# vfd_controller_com.net
KiCad netlist of a schematic drawn in EAGLE
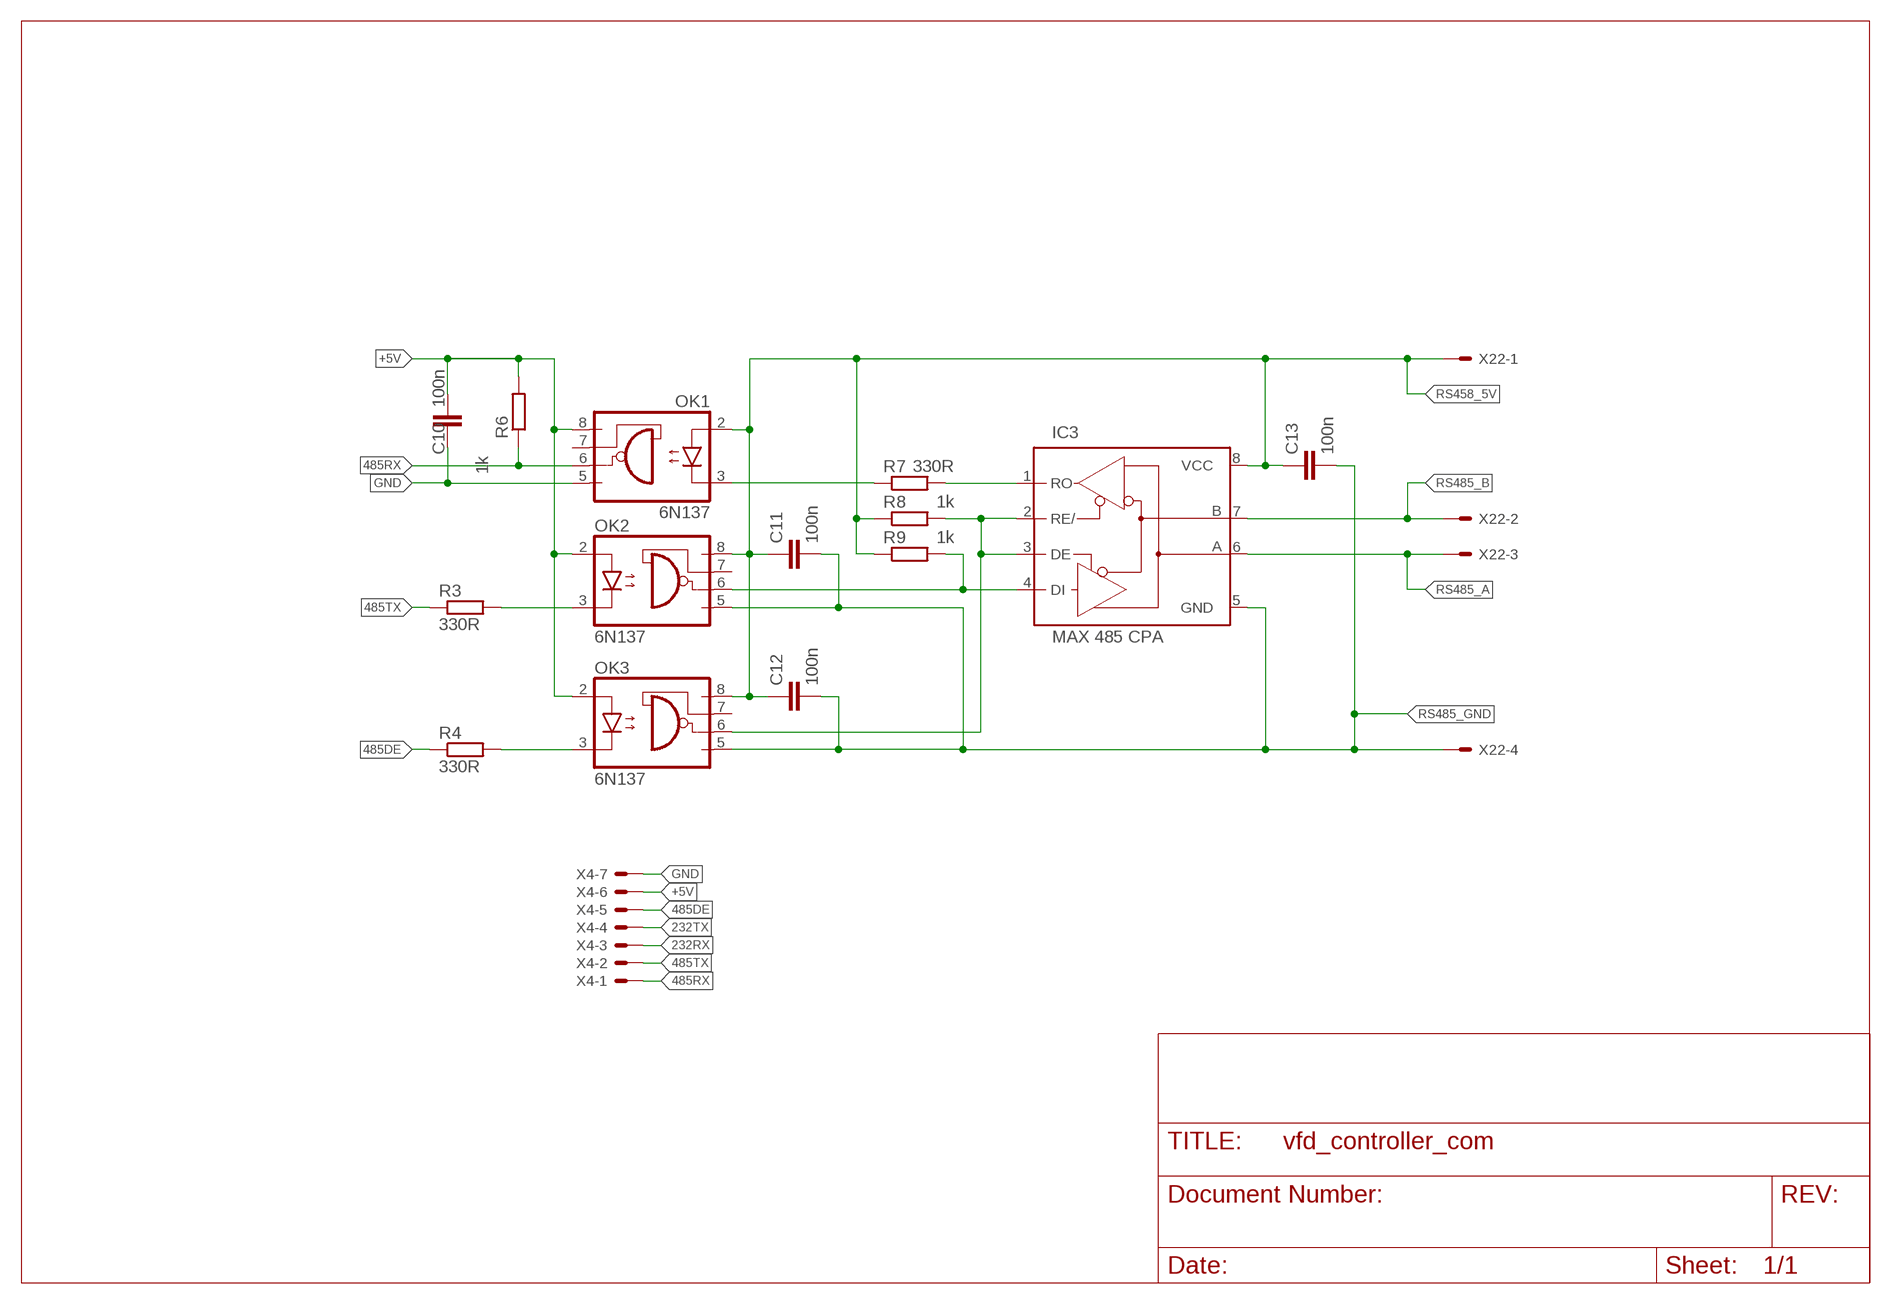
[diagram p0: schematic, sheet 1]

(export (version "E")
  (design (tool "Eeschema 10.0.6"))
  (components
    (comp (ref "C10")
      (value "100n")
      (footprint "eagle-import:C025-024X044")
      (libsource (lib "eagle-import") (part "C-EU025-024X044"))
    )
    (comp (ref "C11")
      (value "100n")
      (footprint "eagle-import:C025-024X044")
      (libsource (lib "eagle-import") (part "C-EU025-024X044"))
    )
    (comp (ref "C12")
      (value "100n")
      (footprint "eagle-import:C025-024X044")
      (libsource (lib "eagle-import") (part "C-EU025-024X044"))
    )
    (comp (ref "C13")
      (value "100n")
      (footprint "eagle-import:C025-024X044")
      (libsource (lib "eagle-import") (part "C-EU025-024X044"))
    )
    (comp (ref "IC3")
      (value "MAX 485 CPA")
      (footprint "eagle-import:DIL08")
      (libsource (lib "eagle-import") (part "MAX34PA68C"))
    )
    (comp (ref "OK1")
      (value "6N137")
      (footprint "eagle-import:DIL08")
      (libsource (lib "eagle-import") (part "6N137"))
    )
    (comp (ref "OK2")
      (value "6N137")
      (footprint "eagle-import:DIL08")
      (libsource (lib "eagle-import") (part "6N137"))
    )
    (comp (ref "OK3")
      (value "6N137")
      (footprint "eagle-import:DIL08")
      (libsource (lib "eagle-import") (part "6N137"))
    )
    (comp (ref "R3")
      (value "330R")
      (footprint "eagle-import:0204_7")
      (libsource (lib "eagle-import") (part "R-EU_0204/7"))
    )
    (comp (ref "R4")
      (value "330R")
      (footprint "eagle-import:0204_7")
      (libsource (lib "eagle-import") (part "R-EU_0204/7"))
    )
    (comp (ref "R6")
      (value "1k")
      (footprint "eagle-import:0204_7")
      (libsource (lib "eagle-import") (part "R-EU_0204/7"))
    )
    (comp (ref "R7")
      (value "330R")
      (footprint "eagle-import:0204_7")
      (libsource (lib "eagle-import") (part "R-EU_0204/7"))
    )
    (comp (ref "R8")
      (value "1k")
      (footprint "eagle-import:0204_7")
      (libsource (lib "eagle-import") (part "R-EU_0204/7"))
    )
    (comp (ref "R9")
      (value "1k")
      (footprint "eagle-import:0204_7")
      (libsource (lib "eagle-import") (part "R-EU_0204/7"))
    )
    (comp (ref "X4")
      (value "JST-XH-07-PIN-LONG-PAD")
      (footprint "eagle-import:JST-XH-07-PACKAGE-LONG-PAD")
      (libsource (lib "eagle-import") (part "JST-XH-07-PIN-LONG-PAD"))
    )
    (comp (ref "X22")
      (value "JST-XH-04-PIN-LONG-PAD")
      (footprint "eagle-import:JST-XH-04-PACKAGE-LONG-PAD")
      (libsource (lib "eagle-import") (part "JST-XH-04-PIN-LONG-PAD"))
    )
  )
  (nets
    (net (code "1") (name "+5V") (class "Default")
      (node (ref "C10") (pin "2") (pinfunction "2_2") (pintype "passive"))
      (node (ref "OK1") (pin "8") (pinfunction "VCC_8") (pintype "passive"))
      (node (ref "OK2") (pin "2") (pinfunction "A_2") (pintype "passive"))
      (node (ref "OK3") (pin "2") (pinfunction "A_2") (pintype "passive"))
      (node (ref "R6") (pin "2") (pinfunction "2_2") (pintype "passive"))
      (node (ref "X4") (pin "6") (pinfunction "S_6") (pintype "passive"))
    )
    (net (code "2") (name "232RX") (class "Default")
      (node (ref "X4") (pin "3") (pinfunction "S_3") (pintype "passive"))
    )
    (net (code "3") (name "232TX") (class "Default")
      (node (ref "X4") (pin "4") (pinfunction "S_4") (pintype "passive"))
    )
    (net (code "4") (name "485DE") (class "Default")
      (node (ref "R4") (pin "1") (pinfunction "1_1") (pintype "passive"))
      (node (ref "X4") (pin "5") (pinfunction "S_5") (pintype "passive"))
    )
    (net (code "5") (name "485RX") (class "Default")
      (node (ref "OK1") (pin "6") (pinfunction "VO_6") (pintype "passive"))
      (node (ref "R6") (pin "1") (pinfunction "1_1") (pintype "passive"))
      (node (ref "X4") (pin "1") (pinfunction "S_1") (pintype "passive"))
    )
    (net (code "6") (name "485TX") (class "Default")
      (node (ref "R3") (pin "1") (pinfunction "1_1") (pintype "passive"))
      (node (ref "X4") (pin "2") (pinfunction "S_2") (pintype "passive"))
    )
    (net (code "7") (name "GND") (class "Default")
      (node (ref "C10") (pin "1") (pinfunction "1_1") (pintype "passive"))
      (node (ref "OK1") (pin "5") (pinfunction "GND_5") (pintype "passive"))
      (node (ref "X4") (pin "7") (pinfunction "S_7") (pintype "passive"))
    )
    (net (code "8") (name "Net-(IC3-DE)") (class "Default")
      (node (ref "IC3") (pin "2") (pinfunction "RE/_2") (pintype "input"))
      (node (ref "IC3") (pin "3") (pinfunction "DE_3") (pintype "input"))
      (node (ref "OK3") (pin "6") (pinfunction "VO_6") (pintype "passive"))
      (node (ref "R8") (pin "2") (pinfunction "2_2") (pintype "passive"))
    )
    (net (code "9") (name "Net-(IC3-DI)") (class "Default")
      (node (ref "IC3") (pin "4") (pinfunction "DI_4") (pintype "input"))
      (node (ref "OK2") (pin "6") (pinfunction "VO_6") (pintype "passive"))
      (node (ref "R9") (pin "2") (pinfunction "2_2") (pintype "passive"))
    )
    (net (code "10") (name "Net-(IC3-RO)") (class "Default")
      (node (ref "IC3") (pin "1") (pinfunction "RO_1") (pintype "output"))
      (node (ref "R7") (pin "2") (pinfunction "2_2") (pintype "passive"))
    )
    (net (code "11") (name "Net-(OK1-C)") (class "Default")
      (node (ref "OK1") (pin "3") (pinfunction "C_3") (pintype "passive"))
      (node (ref "R7") (pin "1") (pinfunction "1_1") (pintype "passive"))
    )
    (net (code "12") (name "Net-(OK2-C)") (class "Default")
      (node (ref "OK2") (pin "3") (pinfunction "C_3") (pintype "passive"))
      (node (ref "R3") (pin "2") (pinfunction "2_2") (pintype "passive"))
    )
    (net (code "13") (name "Net-(OK3-C)") (class "Default")
      (node (ref "OK3") (pin "3") (pinfunction "C_3") (pintype "passive"))
      (node (ref "R4") (pin "2") (pinfunction "2_2") (pintype "passive"))
    )
    (net (code "14") (name "RS458_5V") (class "Default")
      (node (ref "C11") (pin "1") (pinfunction "1_1") (pintype "passive"))
      (node (ref "C12") (pin "1") (pinfunction "1_1") (pintype "passive"))
      (node (ref "C13") (pin "1") (pinfunction "1_1") (pintype "passive"))
      (node (ref "IC3") (pin "8") (pinfunction "VCC_8") (pintype "power_in"))
      (node (ref "OK1") (pin "2") (pinfunction "A_2") (pintype "passive"))
      (node (ref "OK2") (pin "8") (pinfunction "VCC_8") (pintype "passive"))
      (node (ref "OK3") (pin "8") (pinfunction "VCC_8") (pintype "passive"))
      (node (ref "R8") (pin "1") (pinfunction "1_1") (pintype "passive"))
      (node (ref "R9") (pin "1") (pinfunction "1_1") (pintype "passive"))
      (node (ref "X22") (pin "1") (pinfunction "S_1") (pintype "passive"))
    )
    (net (code "15") (name "RS485_A") (class "Default")
      (node (ref "IC3") (pin "6") (pinfunction "A_6") (pintype "passive"))
      (node (ref "X22") (pin "3") (pinfunction "S_3") (pintype "passive"))
    )
    (net (code "16") (name "RS485_B") (class "Default")
      (node (ref "IC3") (pin "7") (pinfunction "B_7") (pintype "passive"))
      (node (ref "X22") (pin "2") (pinfunction "S_2") (pintype "passive"))
    )
    (net (code "17") (name "RS485_GND") (class "Default")
      (node (ref "C11") (pin "2") (pinfunction "2_2") (pintype "passive"))
      (node (ref "C12") (pin "2") (pinfunction "2_2") (pintype "passive"))
      (node (ref "C13") (pin "2") (pinfunction "2_2") (pintype "passive"))
      (node (ref "IC3") (pin "5") (pinfunction "GND_5") (pintype "power_in"))
      (node (ref "OK2") (pin "5") (pinfunction "GND_5") (pintype "passive"))
      (node (ref "OK3") (pin "5") (pinfunction "GND_5") (pintype "passive"))
      (node (ref "X22") (pin "4") (pinfunction "S_4") (pintype "passive"))
    )
    (net (code "18") (name "unconnected-(OK1-VE-Pad7)") (class "Default")
      (node (ref "OK1") (pin "7") (pinfunction "VE_7") (pintype "passive"))
    )
    (net (code "19") (name "unconnected-(OK2-VE-Pad7)") (class "Default")
      (node (ref "OK2") (pin "7") (pinfunction "VE_7") (pintype "passive"))
    )
    (net (code "20") (name "unconnected-(OK3-VE-Pad7)") (class "Default")
      (node (ref "OK3") (pin "7") (pinfunction "VE_7") (pintype "passive"))
    )
  )
)
